# RL_load.net
KiCad netlist of a schematic drawn in Altium Designer
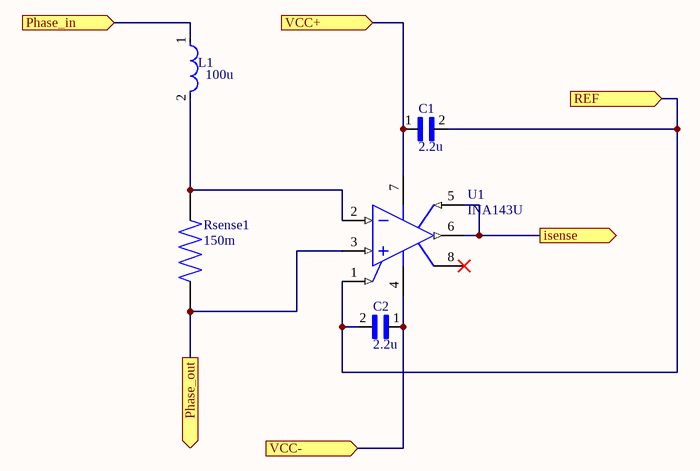
[diagram p0: RL_load.SchDoc]

(export (version "E")
  (design (tool "Eeschema 10.0.6"))
  (components
    (comp (ref "C1")
      (value "2.2u")
      (description "CAP CER 2.2UF 35V X5R 0603")
      (fields
        (field (name "MANUFACTURER") "Murata")
        (field (name "MANUFACTURER PART NUMBER") "GRM188R6YA225MA12D")
      )
      (libsource (lib "") (part "GRM188R6YA225MA12D_1"))
    )
    (comp (ref "C2")
      (value "2.2u")
      (description "CAP CER 2.2UF 35V X5R 0603")
      (fields
        (field (name "MANUFACTURER") "Murata")
        (field (name "MANUFACTURER PART NUMBER") "GRM188R6YA225MA12D")
      )
      (libsource (lib "Schlib_uInv01") (part "GRM188R6YA225MA12D"))
    )
    (comp (ref "L1")
      (value "100u")
      (description "FIXED IND 100UH 5.3A 118 MOHM")
      (fields (field (name "MANUFACTURER") "Pulse") (field (name "MANUFACTURER PART NUMBER") "PA4344.104NLT"))
      (libsource (lib "Schlib_uInv01") (part "PA4344.104NLT"))
    )
    (comp (ref "Rsense1")
      (value "150m")
      (description "Resistor; Wirewound; Res 0.15 Ohms; Pwr-Rtg 5 W; Tol 1%; Axial; Silicone; Cur-Sense")
      (fields (field (name "MANUFACTURER") "Ohmite") (field (name "MANUFACTURER PART NUMBER") "15FR150E"))
      (libsource (lib "Schlib_uInv01") (part "15FR150E"))
    )
    (comp (ref "U1")
      (value "INA143U")
      (description "SP Amp Difference Amplifier Single ±18V/36V 8-Pin SOIC Tube")
      (fields (field (name "MANUFACTURER") "Texas Instruments"))
      (libsource (lib "Schlib_uInv01") (part "INA143U"))
    )
  )
  (nets
    (net (code "1") (name "/Phase_in") (class "Default")
      (node (ref "L1") (pin "1") (pinfunction "1_1") (pintype "passive"))
    )
    (net (code "2") (name "/Phase_out") (class "Default")
      (node (ref "Rsense1") (pin "2") (pinfunction "2_2") (pintype "passive"))
      (node (ref "U1") (pin "3") (pinfunction "IN+_3") (pintype "input"))
    )
    (net (code "3") (name "/REF") (class "Default")
      (node (ref "C1") (pin "2") (pinfunction "2_2") (pintype "passive"))
      (node (ref "C2") (pin "2") (pinfunction "2_2") (pintype "passive"))
      (node (ref "U1") (pin "1") (pinfunction "REF_1") (pintype "input"))
    )
    (net (code "4") (name "/VCC+") (class "Default")
      (node (ref "C1") (pin "1") (pinfunction "1_1") (pintype "passive"))
      (node (ref "U1") (pin "7") (pinfunction "V+_7") (pintype "power_in"))
    )
    (net (code "5") (name "/VCC-") (class "Default")
      (node (ref "C2") (pin "1") (pinfunction "1_1") (pintype "passive"))
      (node (ref "U1") (pin "4") (pinfunction "V-_4") (pintype "power_in"))
    )
    (net (code "6") (name "/isense") (class "Default")
      (node (ref "U1") (pin "5") (pinfunction "SENSE_5") (pintype "input"))
      (node (ref "U1") (pin "6") (pinfunction "OUTPUT_6") (pintype "output"))
    )
    (net (code "7") (name "Net-(U1-IN-)") (class "Default")
      (node (ref "L1") (pin "2") (pinfunction "2_2") (pintype "passive"))
      (node (ref "Rsense1") (pin "1") (pinfunction "1_1") (pintype "passive"))
      (node (ref "U1") (pin "2") (pinfunction "IN-_2") (pintype "input"))
    )
    (net (code "8") (name "unconnected-(U1-NC-Pad8)") (class "Default")
      (node (ref "U1") (pin "8") (pinfunction "NC_8") (pintype "passive+no_connect"))
    )
  )
)
